# LEGOduino.net
KiCad netlist of a schematic drawn in EAGLE
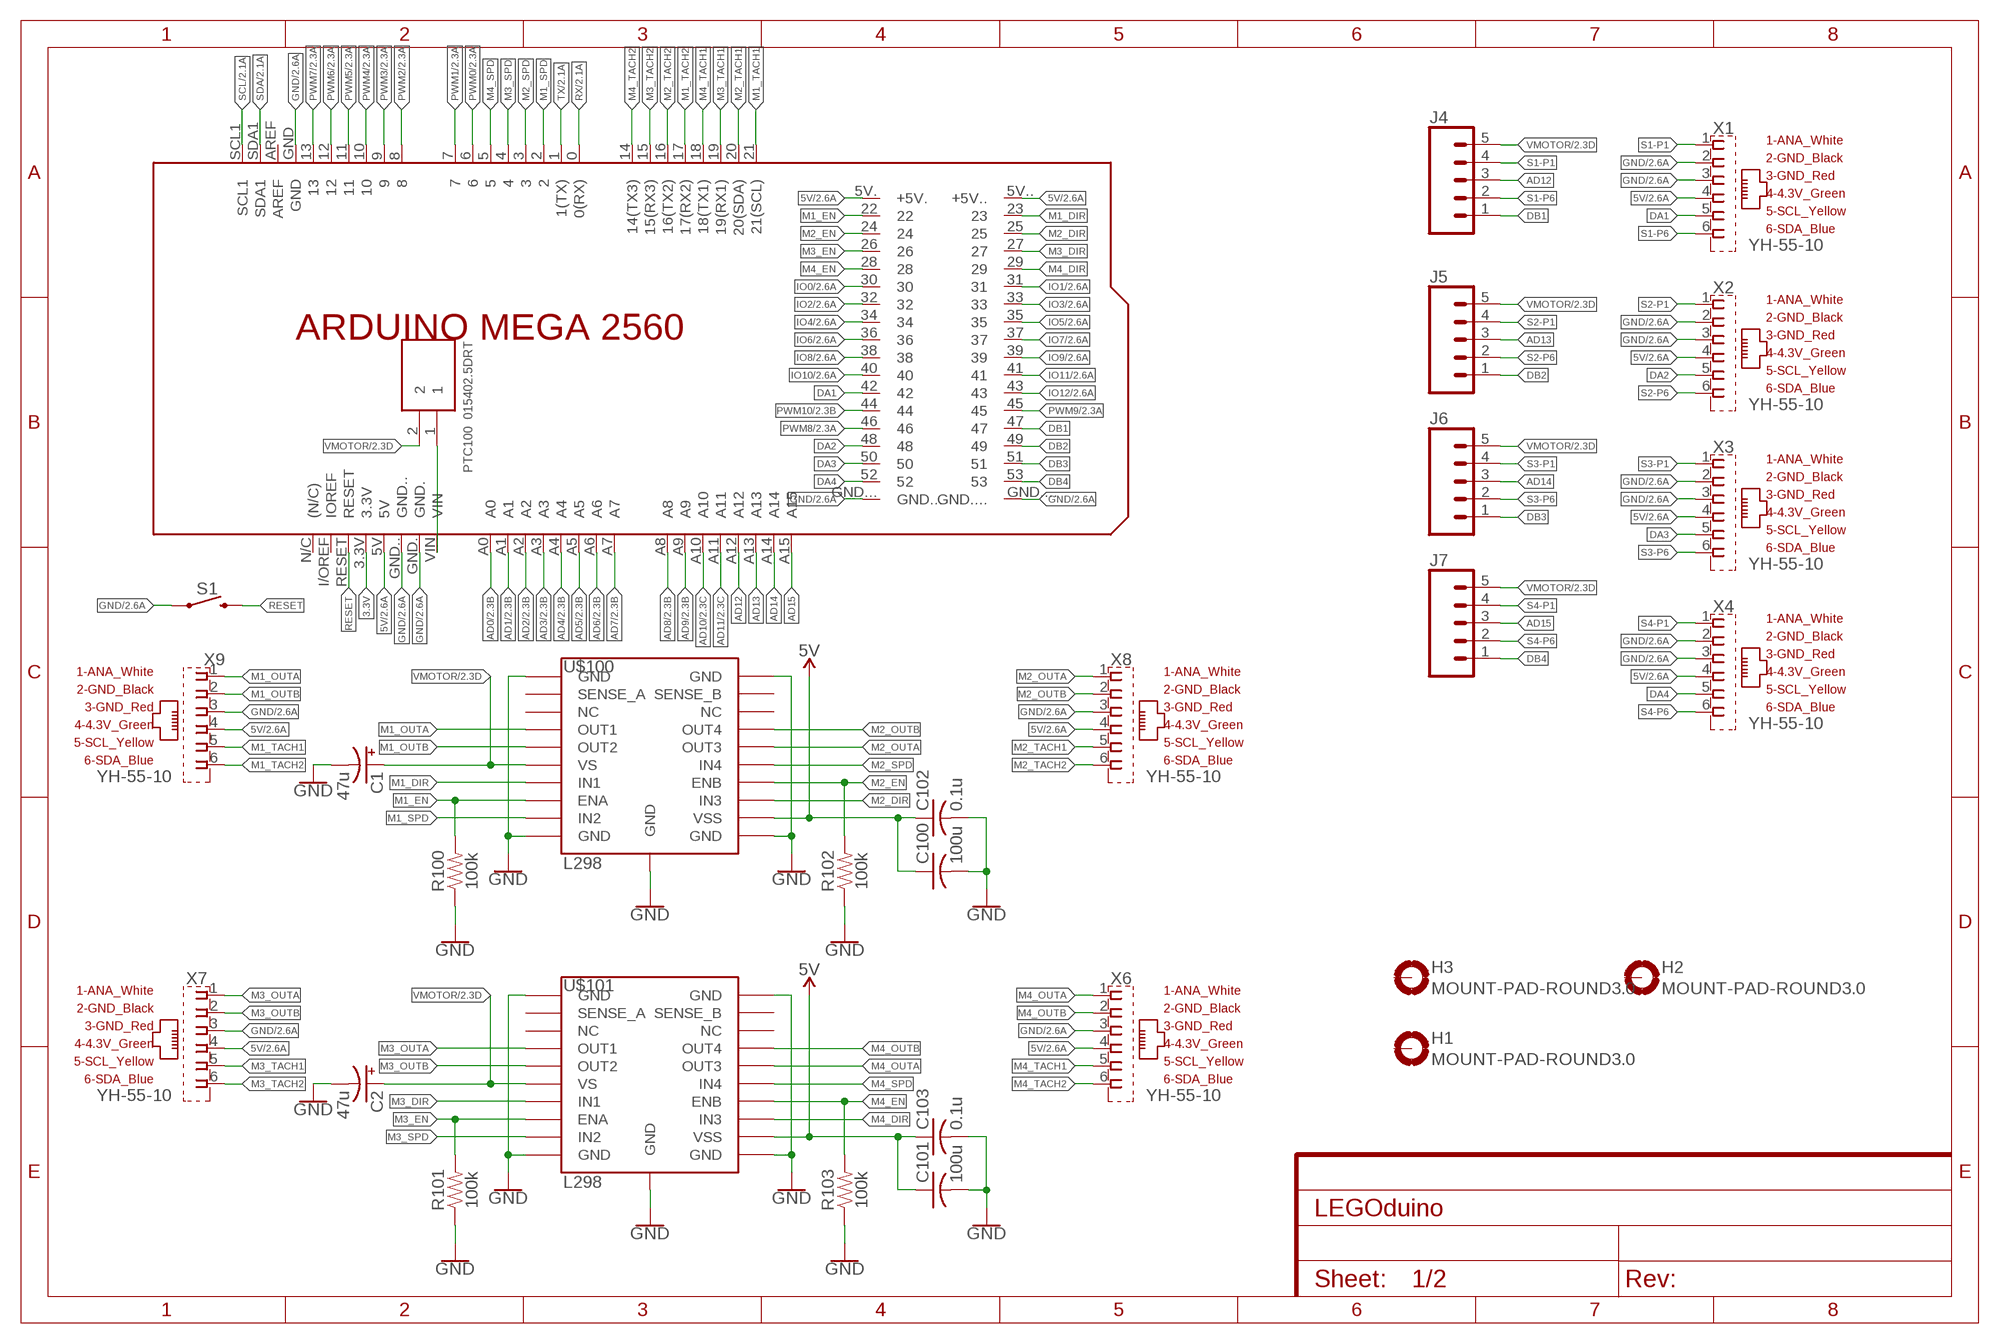
[diagram p0: schematic, sheet 1]
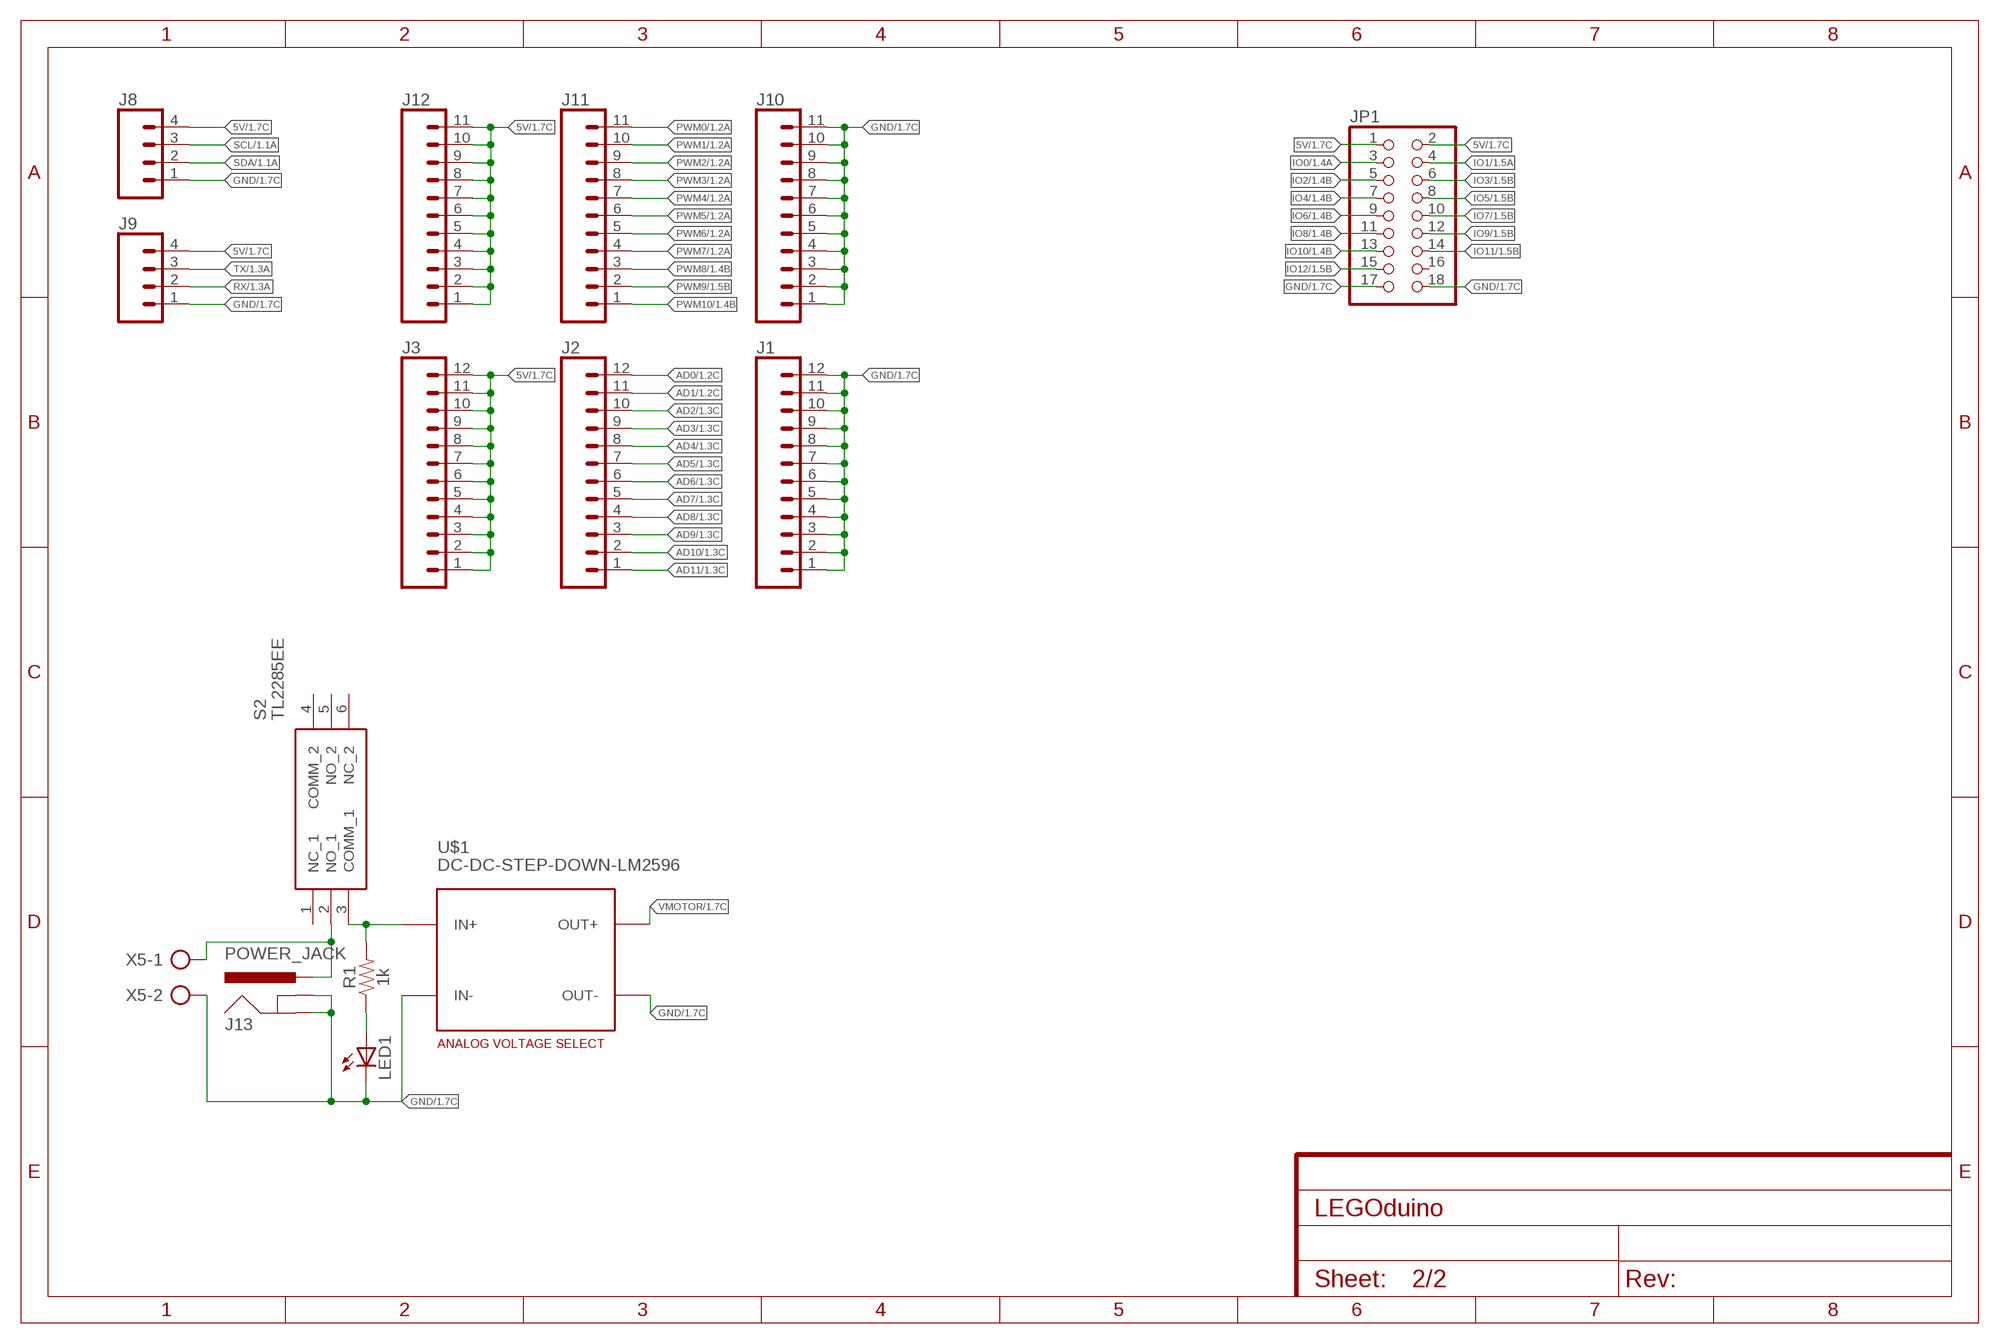
[diagram p1: schematic, sheet 2]

(export (version "E")
  (design (tool "Eeschema 10.0.6"))
  (components
    (comp (ref "J1")
      (value "CONN_12")
      (footprint "eagle-import:1X12")
      (libsource (lib "eagle-import") (part "CONN_12"))
    )
    (comp (ref "J2")
      (value "CONN_12")
      (footprint "eagle-import:1X12")
      (libsource (lib "eagle-import") (part "CONN_12"))
    )
    (comp (ref "J3")
      (value "CONN_12")
      (footprint "eagle-import:1X12")
      (libsource (lib "eagle-import") (part "CONN_12"))
    )
    (comp (ref "J8")
      (value "CONN_04")
      (footprint "eagle-import:1X04")
      (libsource (lib "eagle-import") (part "CONN_04"))
    )
    (comp (ref "J9")
      (value "CONN_04")
      (footprint "eagle-import:1X04")
      (libsource (lib "eagle-import") (part "CONN_04"))
    )
    (comp (ref "J10")
      (value "CONN_11")
      (footprint "eagle-import:1X11")
      (libsource (lib "eagle-import") (part "CONN_11"))
    )
    (comp (ref "J11")
      (value "CONN_11")
      (footprint "eagle-import:1X11")
      (libsource (lib "eagle-import") (part "CONN_11"))
    )
    (comp (ref "J12")
      (value "CONN_11")
      (footprint "eagle-import:1X11")
      (libsource (lib "eagle-import") (part "CONN_11"))
    )
    (comp (ref "J13")
      (value "POWER_JACK")
      (footprint "eagle-import:POWER_JACK_PTH")
      (libsource (lib "eagle-import") (part "POWER_JACK"))
    )
    (comp (ref "JP1")
      (value "PINHD-2X9")
      (footprint "eagle-import:2X09")
      (libsource (lib "eagle-import") (part "PINHD-2X9"))
    )
    (comp (ref "LED1")
      (value "LEDCHIP-LED0805")
      (footprint "eagle-import:CHIP-LED0805")
      (libsource (lib "eagle-import") (part "LEDCHIP-LED0805"))
    )
    (comp (ref "R1")
      (value "1k")
      (footprint "eagle-import:0805")
      (libsource (lib "eagle-import") (part "RESISTOR0805"))
    )
    (comp (ref "S2")
      (value "TL2285EE")
      (footprint "eagle-import:TL2285EE")
      (fields (field (name "MOUSER_PART_NUMBER") "612-TL2285EE"))
      (libsource (lib "eagle-import") (part "TL2285EE"))
    )
    (comp (ref "U$1")
      (value "DC-DC-STEP-DOWN-LM2596")
      (footprint "eagle-import:DC-DC-STEP-DOWN-LM2596")
      (libsource (lib "eagle-import") (part "DC-DC-STEP-DOWN-LM2596"))
    )
    (comp (ref "X5")
      (value "AK500/2-H")
      (footprint "eagle-import:AK500_2-H")
      (libsource (lib "eagle-import") (part "AK500/2-H"))
    )
    (comp (ref "C1")
      (value "47u")
      (footprint "eagle-import:CAPAE830X1050N")
      (libsource (lib "eagle-import") (part "C-POL-USECAP-8.5MM_"))
    )
    (comp (ref "C2")
      (value "47u")
      (footprint "eagle-import:CAPAE830X1050N")
      (libsource (lib "eagle-import") (part "C-POL-USECAP-8.5MM_"))
    )
    (comp (ref "C100")
      (value "100u")
      (footprint "eagle-import:C0805K")
      (libsource (lib "eagle-import") (part "C-USC0805K"))
    )
    (comp (ref "C101")
      (value "100u")
      (footprint "eagle-import:C0805K")
      (libsource (lib "eagle-import") (part "C-USC0805K"))
    )
    (comp (ref "C102")
      (value "0.1u")
      (footprint "eagle-import:C0805K")
      (libsource (lib "eagle-import") (part "C-USC0805K"))
    )
    (comp (ref "C103")
      (value "0.1u")
      (footprint "eagle-import:C0805K")
      (libsource (lib "eagle-import") (part "C-USC0805K"))
    )
    (comp (ref "H1")
      (value "MOUNT-PAD-ROUND3.0")
      (footprint "eagle-import:3,0-PAD")
      (libsource (lib "eagle-import") (part "MOUNT-PAD-ROUND3.0"))
    )
    (comp (ref "H2")
      (value "MOUNT-PAD-ROUND3.0")
      (footprint "eagle-import:3,0-PAD")
      (libsource (lib "eagle-import") (part "MOUNT-PAD-ROUND3.0"))
    )
    (comp (ref "H3")
      (value "MOUNT-PAD-ROUND3.0")
      (footprint "eagle-import:3,0-PAD")
      (libsource (lib "eagle-import") (part "MOUNT-PAD-ROUND3.0"))
    )
    (comp (ref "J4")
      (value "CONN_05")
      (footprint "eagle-import:1X05")
      (libsource (lib "eagle-import") (part "CONN_05"))
    )
    (comp (ref "J5")
      (value "CONN_05")
      (footprint "eagle-import:1X05")
      (libsource (lib "eagle-import") (part "CONN_05"))
    )
    (comp (ref "J6")
      (value "CONN_05")
      (footprint "eagle-import:1X05")
      (libsource (lib "eagle-import") (part "CONN_05"))
    )
    (comp (ref "J7")
      (value "CONN_05")
      (footprint "eagle-import:1X05")
      (libsource (lib "eagle-import") (part "CONN_05"))
    )
    (comp (ref "PCB100")
      (value "ARDUINO_MEGA2560")
      (footprint "eagle-import:ARDUINO_MEGA2560")
      (libsource (lib "eagle-import") (part "ARDUINO_MEGA2560"))
    )
    (comp (ref "PTC100")
      (value "015402.5DRT")
      (footprint "eagle-import:FUSM9750X381N")
      (fields
        (field (name "MOUSER_PART_NUMBER") "576-015402.5DRT")
        (field (name "RS_PART_NUMBER") "7382860P")
      )
      (libsource (lib "eagle-import") (part "015402.5DRT"))
    )
    (comp (ref "R100")
      (value "100k")
      (footprint "eagle-import:0805")
      (libsource (lib "eagle-import") (part "RESISTOR0805"))
    )
    (comp (ref "R101")
      (value "100k")
      (footprint "eagle-import:0805")
      (libsource (lib "eagle-import") (part "RESISTOR0805"))
    )
    (comp (ref "R102")
      (value "100k")
      (footprint "eagle-import:0805")
      (libsource (lib "eagle-import") (part "RESISTOR0805"))
    )
    (comp (ref "R103")
      (value "100k")
      (footprint "eagle-import:0805")
      (libsource (lib "eagle-import") (part "RESISTOR0805"))
    )
    (comp (ref "S1")
      (value "MOMENTARY-SWITCH-SPST-SMD-5.2MM")
      (footprint "eagle-import:TACTILE_SWITCH_SMD_5.2MM")
      (libsource (lib "eagle-import") (part "MOMENTARY-SWITCH-SPST-SMD-5.2MM"))
    )
    (comp (ref "U$100")
      (value "L298")
      (footprint "eagle-import:POWERSO20_L298_PAD")
      (libsource (lib "eagle-import") (part "L298_SMD_W_PAD"))
    )
    (comp (ref "U$101")
      (value "L298")
      (footprint "eagle-import:POWERSO20_L298_PAD")
      (libsource (lib "eagle-import") (part "L298_SMD_W_PAD"))
    )
    (comp (ref "X1")
      (value "YH-55-10")
      (footprint "eagle-import:YH-55-10")
      (libsource (lib "eagle-import") (part "YH-55-10"))
    )
    (comp (ref "X2")
      (value "YH-55-10")
      (footprint "eagle-import:YH-55-10")
      (libsource (lib "eagle-import") (part "YH-55-10"))
    )
    (comp (ref "X3")
      (value "YH-55-10")
      (footprint "eagle-import:YH-55-10")
      (libsource (lib "eagle-import") (part "YH-55-10"))
    )
    (comp (ref "X4")
      (value "YH-55-10")
      (footprint "eagle-import:YH-55-10")
      (libsource (lib "eagle-import") (part "YH-55-10"))
    )
    (comp (ref "X6")
      (value "YH-55-10")
      (footprint "eagle-import:YH-55-10")
      (libsource (lib "eagle-import") (part "YH-55-10"))
    )
    (comp (ref "X7")
      (value "YH-55-10")
      (footprint "eagle-import:YH-55-10")
      (libsource (lib "eagle-import") (part "YH-55-10"))
    )
    (comp (ref "X8")
      (value "YH-55-10")
      (footprint "eagle-import:YH-55-10")
      (libsource (lib "eagle-import") (part "YH-55-10"))
    )
    (comp (ref "X9")
      (value "YH-55-10")
      (footprint "eagle-import:YH-55-10")
      (libsource (lib "eagle-import") (part "YH-55-10"))
    )
  )
  (nets
    (net (code "1") (name "3.3V") (class "Default")
      (node (ref "PCB100") (pin "3.3V") (pinfunction "3.3V_3.3V") (pintype "bidirectional"))
    )
    (net (code "2") (name "5V") (class "Default")
      (node (ref "C100") (pin "1") (pinfunction "1_1") (pintype "passive"))
      (node (ref "C101") (pin "1") (pinfunction "1_1") (pintype "passive"))
      (node (ref "C102") (pin "1") (pinfunction "1_1") (pintype "passive"))
      (node (ref "C103") (pin "1") (pinfunction "1_1") (pintype "passive"))
      (node (ref "J12") (pin "1") (pinfunction "1_1") (pintype "passive"))
      (node (ref "J12") (pin "10") (pinfunction "10_10") (pintype "passive"))
      (node (ref "J12") (pin "11") (pinfunction "11_11") (pintype "passive"))
      (node (ref "J12") (pin "2") (pinfunction "2_2") (pintype "passive"))
      (node (ref "J12") (pin "3") (pinfunction "3_3") (pintype "passive"))
      (node (ref "J12") (pin "4") (pinfunction "4_4") (pintype "passive"))
      (node (ref "J12") (pin "5") (pinfunction "5_5") (pintype "passive"))
      (node (ref "J12") (pin "6") (pinfunction "6_6") (pintype "passive"))
      (node (ref "J12") (pin "7") (pinfunction "7_7") (pintype "passive"))
      (node (ref "J12") (pin "8") (pinfunction "8_8") (pintype "passive"))
      (node (ref "J12") (pin "9") (pinfunction "9_9") (pintype "passive"))
      (node (ref "J3") (pin "1") (pinfunction "1_1") (pintype "passive"))
      (node (ref "J3") (pin "10") (pinfunction "10_10") (pintype "passive"))
      (node (ref "J3") (pin "11") (pinfunction "11_11") (pintype "passive"))
      (node (ref "J3") (pin "12") (pinfunction "12_12") (pintype "passive"))
      (node (ref "J3") (pin "2") (pinfunction "2_2") (pintype "passive"))
      (node (ref "J3") (pin "3") (pinfunction "3_3") (pintype "passive"))
      (node (ref "J3") (pin "4") (pinfunction "4_4") (pintype "passive"))
      (node (ref "J3") (pin "5") (pinfunction "5_5") (pintype "passive"))
      (node (ref "J3") (pin "6") (pinfunction "6_6") (pintype "passive"))
      (node (ref "J3") (pin "7") (pinfunction "7_7") (pintype "passive"))
      (node (ref "J3") (pin "8") (pinfunction "8_8") (pintype "passive"))
      (node (ref "J3") (pin "9") (pinfunction "9_9") (pintype "passive"))
      (node (ref "J8") (pin "4") (pinfunction "4_4") (pintype "passive"))
      (node (ref "J9") (pin "4") (pinfunction "4_4") (pintype "passive"))
      (node (ref "JP1") (pin "1") (pinfunction "1_1") (pintype "passive"))
      (node (ref "JP1") (pin "2") (pinfunction "2_2") (pintype "passive"))
      (node (ref "PCB100") (pin "5V") (pinfunction "5V_5V") (pintype "bidirectional"))
      (node (ref "PCB100") (pin "5V.") (pinfunction "+5V._5V.") (pintype "bidirectional"))
      (node (ref "PCB100") (pin "5V..") (pinfunction "+5V.._5V..") (pintype "bidirectional"))
      (node (ref "U$100") (pin "12") (pinfunction "VSS_12") (pintype "bidirectional"))
      (node (ref "U$101") (pin "12") (pinfunction "VSS_12") (pintype "bidirectional"))
      (node (ref "X1") (pin "4") (pinfunction "4_4.3V_GREEN_4") (pintype "passive"))
      (node (ref "X2") (pin "4") (pinfunction "4_4.3V_GREEN_4") (pintype "passive"))
      (node (ref "X3") (pin "4") (pinfunction "4_4.3V_GREEN_4") (pintype "passive"))
      (node (ref "X4") (pin "4") (pinfunction "4_4.3V_GREEN_4") (pintype "passive"))
      (node (ref "X6") (pin "4") (pinfunction "4_4.3V_GREEN_4") (pintype "passive"))
      (node (ref "X7") (pin "4") (pinfunction "4_4.3V_GREEN_4") (pintype "passive"))
      (node (ref "X8") (pin "4") (pinfunction "4_4.3V_GREEN_4") (pintype "passive"))
      (node (ref "X9") (pin "4") (pinfunction "4_4.3V_GREEN_4") (pintype "passive"))
    )
    (net (code "3") (name "AD0") (class "Default")
      (node (ref "J2") (pin "12") (pinfunction "12_12") (pintype "passive"))
      (node (ref "PCB100") (pin "A0") (pinfunction "A0_A0") (pintype "bidirectional"))
    )
    (net (code "4") (name "AD1") (class "Default")
      (node (ref "J2") (pin "11") (pinfunction "11_11") (pintype "passive"))
      (node (ref "PCB100") (pin "A1") (pinfunction "A1_A1") (pintype "bidirectional"))
    )
    (net (code "5") (name "AD2") (class "Default")
      (node (ref "J2") (pin "10") (pinfunction "10_10") (pintype "passive"))
      (node (ref "PCB100") (pin "A2") (pinfunction "A2_A2") (pintype "bidirectional"))
    )
    (net (code "6") (name "AD3") (class "Default")
      (node (ref "J2") (pin "9") (pinfunction "9_9") (pintype "passive"))
      (node (ref "PCB100") (pin "A3") (pinfunction "A3_A3") (pintype "bidirectional"))
    )
    (net (code "7") (name "AD4") (class "Default")
      (node (ref "J2") (pin "8") (pinfunction "8_8") (pintype "passive"))
      (node (ref "PCB100") (pin "A4") (pinfunction "A4_A4") (pintype "bidirectional"))
    )
    (net (code "8") (name "AD5") (class "Default")
      (node (ref "J2") (pin "7") (pinfunction "7_7") (pintype "passive"))
      (node (ref "PCB100") (pin "A5") (pinfunction "A5_A5") (pintype "bidirectional"))
    )
    (net (code "9") (name "AD6") (class "Default")
      (node (ref "J2") (pin "6") (pinfunction "6_6") (pintype "passive"))
      (node (ref "PCB100") (pin "A6") (pinfunction "A6_A6") (pintype "bidirectional"))
    )
    (net (code "10") (name "AD7") (class "Default")
      (node (ref "J2") (pin "5") (pinfunction "5_5") (pintype "passive"))
      (node (ref "PCB100") (pin "A7") (pinfunction "A7_A7") (pintype "bidirectional"))
    )
    (net (code "11") (name "AD8") (class "Default")
      (node (ref "J2") (pin "4") (pinfunction "4_4") (pintype "passive"))
      (node (ref "PCB100") (pin "A8") (pinfunction "A8_A8") (pintype "bidirectional"))
    )
    (net (code "12") (name "AD9") (class "Default")
      (node (ref "J2") (pin "3") (pinfunction "3_3") (pintype "passive"))
      (node (ref "PCB100") (pin "A9") (pinfunction "A9_A9") (pintype "bidirectional"))
    )
    (net (code "13") (name "AD10") (class "Default")
      (node (ref "J2") (pin "2") (pinfunction "2_2") (pintype "passive"))
      (node (ref "PCB100") (pin "A10") (pinfunction "A10_A10") (pintype "bidirectional"))
    )
    (net (code "14") (name "AD11") (class "Default")
      (node (ref "J2") (pin "1") (pinfunction "1_1") (pintype "passive"))
      (node (ref "PCB100") (pin "A11") (pinfunction "A11_A11") (pintype "bidirectional"))
    )
    (net (code "15") (name "AD12") (class "Default")
      (node (ref "J4") (pin "3") (pinfunction "3_3") (pintype "passive"))
      (node (ref "PCB100") (pin "A12") (pinfunction "A12_A12") (pintype "bidirectional"))
    )
    (net (code "16") (name "AD13") (class "Default")
      (node (ref "J5") (pin "3") (pinfunction "3_3") (pintype "passive"))
      (node (ref "PCB100") (pin "A13") (pinfunction "A13_A13") (pintype "bidirectional"))
    )
    (net (code "17") (name "AD14") (class "Default")
      (node (ref "J6") (pin "3") (pinfunction "3_3") (pintype "passive"))
      (node (ref "PCB100") (pin "A14") (pinfunction "A14_A14") (pintype "bidirectional"))
    )
    (net (code "18") (name "AD15") (class "Default")
      (node (ref "J7") (pin "3") (pinfunction "3_3") (pintype "passive"))
      (node (ref "PCB100") (pin "A15") (pinfunction "A15_A15") (pintype "bidirectional"))
    )
    (net (code "19") (name "DA1") (class "Default")
      (node (ref "PCB100") (pin "42") (pinfunction "42_42") (pintype "bidirectional"))
      (node (ref "X1") (pin "5") (pinfunction "5_SCL_YELLOW_5") (pintype "passive"))
    )
    (net (code "20") (name "DA2") (class "Default")
      (node (ref "PCB100") (pin "48") (pinfunction "48_48") (pintype "bidirectional"))
      (node (ref "X2") (pin "5") (pinfunction "5_SCL_YELLOW_5") (pintype "passive"))
    )
    (net (code "21") (name "DA3") (class "Default")
      (node (ref "PCB100") (pin "50") (pinfunction "50_50") (pintype "bidirectional"))
      (node (ref "X3") (pin "5") (pinfunction "5_SCL_YELLOW_5") (pintype "passive"))
    )
    (net (code "22") (name "DA4") (class "Default")
      (node (ref "PCB100") (pin "52") (pinfunction "52_52") (pintype "bidirectional"))
      (node (ref "X4") (pin "5") (pinfunction "5_SCL_YELLOW_5") (pintype "passive"))
    )
    (net (code "23") (name "DB1") (class "Default")
      (node (ref "J4") (pin "1") (pinfunction "1_1") (pintype "passive"))
      (node (ref "PCB100") (pin "47") (pinfunction "47_47") (pintype "bidirectional"))
    )
    (net (code "24") (name "DB2") (class "Default")
      (node (ref "J5") (pin "1") (pinfunction "1_1") (pintype "passive"))
      (node (ref "PCB100") (pin "49") (pinfunction "49_49") (pintype "bidirectional"))
    )
    (net (code "25") (name "DB3") (class "Default")
      (node (ref "J6") (pin "1") (pinfunction "1_1") (pintype "passive"))
      (node (ref "PCB100") (pin "51") (pinfunction "51_51") (pintype "bidirectional"))
    )
    (net (code "26") (name "DB4") (class "Default")
      (node (ref "J7") (pin "1") (pinfunction "1_1") (pintype "passive"))
      (node (ref "PCB100") (pin "53") (pinfunction "53_53") (pintype "bidirectional"))
    )
    (net (code "27") (name "GND") (class "Default")
      (node (ref "C1") (pin "2") (pinfunction "-_2") (pintype "passive"))
      (node (ref "C100") (pin "2") (pinfunction "2_2") (pintype "passive"))
      (node (ref "C101") (pin "2") (pinfunction "2_2") (pintype "passive"))
      (node (ref "C102") (pin "2") (pinfunction "2_2") (pintype "passive"))
      (node (ref "C103") (pin "2") (pinfunction "2_2") (pintype "passive"))
      (node (ref "C2") (pin "2") (pinfunction "-_2") (pintype "passive"))
      (node (ref "J1") (pin "1") (pinfunction "1_1") (pintype "passive"))
      (node (ref "J1") (pin "10") (pinfunction "10_10") (pintype "passive"))
      (node (ref "J1") (pin "11") (pinfunction "11_11") (pintype "passive"))
      (node (ref "J1") (pin "12") (pinfunction "12_12") (pintype "passive"))
      (node (ref "J1") (pin "2") (pinfunction "2_2") (pintype "passive"))
      (node (ref "J1") (pin "3") (pinfunction "3_3") (pintype "passive"))
      (node (ref "J1") (pin "4") (pinfunction "4_4") (pintype "passive"))
      (node (ref "J1") (pin "5") (pinfunction "5_5") (pintype "passive"))
      (node (ref "J1") (pin "6") (pinfunction "6_6") (pintype "passive"))
      (node (ref "J1") (pin "7") (pinfunction "7_7") (pintype "passive"))
      (node (ref "J1") (pin "8") (pinfunction "8_8") (pintype "passive"))
      (node (ref "J1") (pin "9") (pinfunction "9_9") (pintype "passive"))
      (node (ref "J10") (pin "1") (pinfunction "1_1") (pintype "passive"))
      (node (ref "J10") (pin "10") (pinfunction "10_10") (pintype "passive"))
      (node (ref "J10") (pin "11") (pinfunction "11_11") (pintype "passive"))
      (node (ref "J10") (pin "2") (pinfunction "2_2") (pintype "passive"))
      (node (ref "J10") (pin "3") (pinfunction "3_3") (pintype "passive"))
      (node (ref "J10") (pin "4") (pinfunction "4_4") (pintype "passive"))
      (node (ref "J10") (pin "5") (pinfunction "5_5") (pintype "passive"))
      (node (ref "J10") (pin "6") (pinfunction "6_6") (pintype "passive"))
      (node (ref "J10") (pin "7") (pinfunction "7_7") (pintype "passive"))
      (node (ref "J10") (pin "8") (pinfunction "8_8") (pintype "passive"))
      (node (ref "J10") (pin "9") (pinfunction "9_9") (pintype "passive"))
      (node (ref "J13") (pin "GND") (pinfunction "GND_GND") (pintype "bidirectional"))
      (node (ref "J13") (pin "GNDBREAK") (pinfunction "GNDBREAK_GNDBREAK") (pintype "bidirectional"))
      (node (ref "J8") (pin "1") (pinfunction "1_1") (pintype "passive"))
      (node (ref "J9") (pin "1") (pinfunction "1_1") (pintype "passive"))
      (node (ref "JP1") (pin "17") (pinfunction "17_17") (pintype "passive"))
      (node (ref "JP1") (pin "18") (pinfunction "18_18") (pintype "passive"))
      (node (ref "LED1") (pin "C") (pinfunction "C_C") (pintype "passive"))
      (node (ref "PCB100") (pin "GND") (pinfunction "GND_GND") (pintype "bidirectional"))
      (node (ref "PCB100") (pin "GND.") (pinfunction "GND._GND.") (pintype "bidirectional"))
      (node (ref "PCB100") (pin "GND..") (pinfunction "GND.._GND..") (pintype "bidirectional"))
      (node (ref "PCB100") (pin "GND...") (pinfunction "GND..._GND...") (pintype "bidirectional"))
      (node (ref "PCB100") (pin "GND....") (pinfunction "GND...._GND....") (pintype "bidirectional"))
      (node (ref "R100") (pin "1") (pinfunction "1_1") (pintype "passive"))
      (node (ref "R101") (pin "1") (pinfunction "1_1") (pintype "passive"))
      (node (ref "R102") (pin "1") (pinfunction "1_1") (pintype "passive"))
      (node (ref "R103") (pin "1") (pinfunction "1_1") (pintype "passive"))
      (node (ref "S1") (pin "1") (pinfunction "1_1") (pintype "passive"))
      (node (ref "U$1") (pin "IN-") (pinfunction "IN-_IN-") (pintype "bidirectional"))
      (node (ref "U$1") (pin "OUT-") (pinfunction "OUT-_OUT-") (pintype "bidirectional"))
      (node (ref "U$100") (pin "1") (pinfunction "GND_1") (pintype "bidirectional"))
      (node (ref "U$100") (pin "10") (pinfunction "GND_10") (pintype "bidirectional"))
      (node (ref "U$100") (pin "11") (pinfunction "GND_11") (pintype "bidirectional"))
      (node (ref "U$100") (pin "20") (pinfunction "GND_20") (pintype "bidirectional"))
      (node (ref "U$100") (pin "PAD") (pinfunction "GND_PAD") (pintype "bidirectional"))
      (node (ref "U$101") (pin "1") (pinfunction "GND_1") (pintype "bidirectional"))
      (node (ref "U$101") (pin "10") (pinfunction "GND_10") (pintype "bidirectional"))
      (node (ref "U$101") (pin "11") (pinfunction "GND_11") (pintype "bidirectional"))
      (node (ref "U$101") (pin "20") (pinfunction "GND_20") (pintype "bidirectional"))
      (node (ref "U$101") (pin "PAD") (pinfunction "GND_PAD") (pintype "bidirectional"))
      (node (ref "X1") (pin "2") (pinfunction "2_GND_BLACK_2") (pintype "passive"))
      (node (ref "X1") (pin "3") (pinfunction "3_GND_RED_3") (pintype "passive"))
      (node (ref "X2") (pin "2") (pinfunction "2_GND_BLACK_2") (pintype "passive"))
      (node (ref "X2") (pin "3") (pinfunction "3_GND_RED_3") (pintype "passive"))
      (node (ref "X3") (pin "2") (pinfunction "2_GND_BLACK_2") (pintype "passive"))
      (node (ref "X3") (pin "3") (pinfunction "3_GND_RED_3") (pintype "passive"))
      (node (ref "X4") (pin "2") (pinfunction "2_GND_BLACK_2") (pintype "passive"))
      (node (ref "X4") (pin "3") (pinfunction "3_GND_RED_3") (pintype "passive"))
      (node (ref "X5") (pin "2") (pinfunction "KL_2") (pintype "passive"))
      (node (ref "X6") (pin "3") (pinfunction "3_GND_RED_3") (pintype "passive"))
      (node (ref "X7") (pin "3") (pinfunction "3_GND_RED_3") (pintype "passive"))
      (node (ref "X8") (pin "3") (pinfunction "3_GND_RED_3") (pintype "passive"))
      (node (ref "X9") (pin "3") (pinfunction "3_GND_RED_3") (pintype "passive"))
    )
    (net (code "28") (name "IO0") (class "Default")
      (node (ref "JP1") (pin "3") (pinfunction "3_3") (pintype "passive"))
      (node (ref "PCB100") (pin "30") (pinfunction "30_30") (pintype "bidirectional"))
    )
    (net (code "29") (name "IO1") (class "Default")
      (node (ref "JP1") (pin "4") (pinfunction "4_4") (pintype "passive"))
      (node (ref "PCB100") (pin "31") (pinfunction "31_31") (pintype "bidirectional"))
    )
    (net (code "30") (name "IO2") (class "Default")
      (node (ref "JP1") (pin "5") (pinfunction "5_5") (pintype "passive"))
      (node (ref "PCB100") (pin "32") (pinfunction "32_32") (pintype "bidirectional"))
    )
    (net (code "31") (name "IO3") (class "Default")
      (node (ref "JP1") (pin "6") (pinfunction "6_6") (pintype "passive"))
      (node (ref "PCB100") (pin "33") (pinfunction "33_33") (pintype "bidirectional"))
    )
    (net (code "32") (name "IO4") (class "Default")
      (node (ref "JP1") (pin "7") (pinfunction "7_7") (pintype "passive"))
      (node (ref "PCB100") (pin "34") (pinfunction "34_34") (pintype "bidirectional"))
    )
    (net (code "33") (name "IO5") (class "Default")
      (node (ref "JP1") (pin "8") (pinfunction "8_8") (pintype "passive"))
      (node (ref "PCB100") (pin "35") (pinfunction "35_35") (pintype "bidirectional"))
    )
    (net (code "34") (name "IO6") (class "Default")
      (node (ref "JP1") (pin "9") (pinfunction "9_9") (pintype "passive"))
      (node (ref "PCB100") (pin "36") (pinfunction "36_36") (pintype "bidirectional"))
    )
    (net (code "35") (name "IO7") (class "Default")
      (node (ref "JP1") (pin "10") (pinfunction "10_10") (pintype "passive"))
      (node (ref "PCB100") (pin "37") (pinfunction "37_37") (pintype "bidirectional"))
    )
    (net (code "36") (name "IO8") (class "Default")
      (node (ref "JP1") (pin "11") (pinfunction "11_11") (pintype "passive"))
      (node (ref "PCB100") (pin "38") (pinfunction "38_38") (pintype "bidirectional"))
    )
    (net (code "37") (name "IO9") (class "Default")
      (node (ref "JP1") (pin "12") (pinfunction "12_12") (pintype "passive"))
      (node (ref "PCB100") (pin "39") (pinfunction "39_39") (pintype "bidirectional"))
    )
    (net (code "38") (name "IO10") (class "Default")
      (node (ref "JP1") (pin "13") (pinfunction "13_13") (pintype "passive"))
      (node (ref "PCB100") (pin "40") (pinfunction "40_40") (pintype "bidirectional"))
    )
    (net (code "39") (name "IO11") (class "Default")
      (node (ref "JP1") (pin "14") (pinfunction "14_14") (pintype "passive"))
      (node (ref "PCB100") (pin "41") (pinfunction "41_41") (pintype "bidirectional"))
    )
    (net (code "40") (name "IO12") (class "Default")
      (node (ref "JP1") (pin "15") (pinfunction "15_15") (pintype "passive"))
      (node (ref "PCB100") (pin "43") (pinfunction "43_43") (pintype "bidirectional"))
    )
    (net (code "41") (name "M1_DIR") (class "Default")
      (node (ref "PCB100") (pin "23") (pinfunction "23_23") (pintype "bidirectional"))
      (node (ref "U$100") (pin "7") (pinfunction "IN1_7") (pintype "bidirectional"))
    )
    (net (code "42") (name "M1_EN") (class "Default")
      (node (ref "PCB100") (pin "22") (pinfunction "22_22") (pintype "bidirectional"))
      (node (ref "R100") (pin "2") (pinfunction "2_2") (pintype "passive"))
      (node (ref "U$100") (pin "8") (pinfunction "ENA_8") (pintype "bidirectional"))
    )
    (net (code "43") (name "M1_OUTA") (class "Default")
      (node (ref "U$100") (pin "4") (pinfunction "OUT1_4") (pintype "bidirectional"))
      (node (ref "X9") (pin "1") (pinfunction "1_ANA_WHITE_1") (pintype "passive"))
    )
    (net (code "44") (name "M1_OUTB") (class "Default")
      (node (ref "U$100") (pin "5") (pinfunction "OUT2_5") (pintype "bidirectional"))
      (node (ref "X9") (pin "2") (pinfunction "2_GND_BLACK_2") (pintype "passive"))
    )
    (net (code "45") (name "M1_SPD") (class "Default")
      (node (ref "PCB100") (pin "2") (pinfunction "2_2") (pintype "bidirectional"))
      (node (ref "U$100") (pin "9") (pinfunction "IN2_9") (pintype "bidirectional"))
    )
    (net (code "46") (name "M1_TACH1") (class "Default")
      (node (ref "PCB100") (pin "21") (pinfunction "21(SCL)_21") (pintype "bidirectional"))
      (node (ref "X9") (pin "5") (pinfunction "5_SCL_YELLOW_5") (pintype "passive"))
    )
    (net (code "47") (name "M1_TACH2") (class "Default")
      (node (ref "PCB100") (pin "17") (pinfunction "17(RX2)_17") (pintype "bidirectional"))
      (node (ref "X9") (pin "6") (pinfunction "6_SDA_BLUE_6") (pintype "passive"))
    )
    (net (code "48") (name "M2_DIR") (class "Default")
      (node (ref "PCB100") (pin "25") (pinfunction "25_25") (pintype "bidirectional"))
      (node (ref "U$100") (pin "13") (pinfunction "IN3_13") (pintype "bidirectional"))
    )
    (net (code "49") (name "M2_EN") (class "Default")
      (node (ref "PCB100") (pin "24") (pinfunction "24_24") (pintype "bidirectional"))
      (node (ref "R102") (pin "2") (pinfunction "2_2") (pintype "passive"))
      (node (ref "U$100") (pin "14") (pinfunction "ENB_14") (pintype "bidirectional"))
    )
    (net (code "50") (name "M2_OUTA") (class "Default")
      (node (ref "U$100") (pin "16") (pinfunction "OUT3_16") (pintype "bidirectional"))
      (node (ref "X8") (pin "1") (pinfunction "1_ANA_WHITE_1") (pintype "passive"))
    )
    (net (code "51") (name "M2_OUTB") (class "Default")
      (node (ref "U$100") (pin "17") (pinfunction "OUT4_17") (pintype "bidirectional"))
      (node (ref "X8") (pin "2") (pinfunction "2_GND_BLACK_2") (pintype "passive"))
    )
    (net (code "52") (name "M2_SPD") (class "Default")
      (node (ref "PCB100") (pin "3") (pinfunction "3_3") (pintype "bidirectional"))
      (node (ref "U$100") (pin "15") (pinfunction "IN4_15") (pintype "bidirectional"))
    )
    (net (code "53") (name "M2_TACH1") (class "Default")
      (node (ref "PCB100") (pin "20") (pinfunction "20(SDA)_20") (pintype "bidirectional"))
      (node (ref "X8") (pin "5") (pinfunction "5_SCL_YELLOW_5") (pintype "passive"))
    )
    (net (code "54") (name "M2_TACH2") (class "Default")
      (node (ref "PCB100") (pin "16") (pinfunction "16(TX2)_16") (pintype "bidirectional"))
      (node (ref "X8") (pin "6") (pinfunction "6_SDA_BLUE_6") (pintype "passive"))
    )
    (net (code "55") (name "M3_DIR") (class "Default")
      (node (ref "PCB100") (pin "27") (pinfunction "27_27") (pintype "bidirectional"))
      (node (ref "U$101") (pin "7") (pinfunction "IN1_7") (pintype "bidirectional"))
    )
    (net (code "56") (name "M3_EN") (class "Default")
      (node (ref "PCB100") (pin "26") (pinfunction "26_26") (pintype "bidirectional"))
      (node (ref "R101") (pin "2") (pinfunction "2_2") (pintype "passive"))
      (node (ref "U$101") (pin "8") (pinfunction "ENA_8") (pintype "bidirectional"))
    )
    (net (code "57") (name "M3_OUTA") (class "Default")
      (node (ref "U$101") (pin "4") (pinfunction "OUT1_4") (pintype "bidirectional"))
      (node (ref "X7") (pin "1") (pinfunction "1_ANA_WHITE_1") (pintype "passive"))
    )
    (net (code "58") (name "M3_OUTB") (class "Default")
      (node (ref "U$101") (pin "5") (pinfunction "OUT2_5") (pintype "bidirectional"))
      (node (ref "X7") (pin "2") (pinfunction "2_GND_BLACK_2") (pintype "passive"))
    )
    (net (code "59") (name "M3_SPD") (class "Default")
      (node (ref "PCB100") (pin "4") (pinfunction "4_4") (pintype "bidirectional"))
      (node (ref "U$101") (pin "9") (pinfunction "IN2_9") (pintype "bidirectional"))
    )
    (net (code "60") (name "M3_TACH1") (class "Default")
      (node (ref "PCB100") (pin "19") (pinfunction "19(RX1)_19") (pintype "bidirectional"))
      (node (ref "X7") (pin "5") (pinfunction "5_SCL_YELLOW_5") (pintype "passive"))
    )
    (net (code "61") (name "M3_TACH2") (class "Default")
      (node (ref "PCB100") (pin "15") (pinfunction "15(RX3)_15") (pintype "bidirectional"))
      (node (ref "X7") (pin "6") (pinfunction "6_SDA_BLUE_6") (pintype "passive"))
    )
    (net (code "62") (name "M4_DIR") (class "Default")
      (node (ref "PCB100") (pin "29") (pinfunction "29_29") (pintype "bidirectional"))
      (node (ref "U$101") (pin "13") (pinfunction "IN3_13") (pintype "bidirectional"))
    )
    (net (code "63") (name "M4_EN") (class "Default")
      (node (ref "PCB100") (pin "28") (pinfunction "28_28") (pintype "bidirectional"))
      (node (ref "R103") (pin "2") (pinfunction "2_2") (pintype "passive"))
      (node (ref "U$101") (pin "14") (pinfunction "ENB_14") (pintype "bidirectional"))
    )
    (net (code "64") (name "M4_OUTA") (class "Default")
      (node (ref "U$101") (pin "16") (pinfunction "OUT3_16") (pintype "bidirectional"))
      (node (ref "X6") (pin "1") (pinfunction "1_ANA_WHITE_1") (pintype "passive"))
    )
    (net (code "65") (name "M4_OUTB") (class "Default")
      (node (ref "U$101") (pin "17") (pinfunction "OUT4_17") (pintype "bidirectional"))
      (node (ref "X6") (pin "2") (pinfunction "2_GND_BLACK_2") (pintype "passive"))
    )
    (net (code "66") (name "M4_SPD") (class "Default")
      (node (ref "PCB100") (pin "5") (pinfunction "5_5") (pintype "bidirectional"))
      (node (ref "U$101") (pin "15") (pinfunction "IN4_15") (pintype "bidirectional"))
    )
    (net (code "67") (name "M4_TACH1") (class "Default")
      (node (ref "PCB100") (pin "18") (pinfunction "18(TX1)_18") (pintype "bidirectional"))
      (node (ref "X6") (pin "5") (pinfunction "5_SCL_YELLOW_5") (pintype "passive"))
    )
    (net (code "68") (name "M4_TACH2") (class "Default")
      (node (ref "PCB100") (pin "14") (pinfunction "14(TX3)_14") (pintype "bidirectional"))
      (node (ref "X6") (pin "6") (pinfunction "6_SDA_BLUE_6") (pintype "passive"))
    )
    (net (code "69") (name "Net-(LED1-PadA)") (class "Default")
      (node (ref "LED1") (pin "A") (pinfunction "A_A") (pintype "passive"))
      (node (ref "R1") (pin "1") (pinfunction "1_1") (pintype "passive"))
    )
    (net (code "70") (name "Net-(PCB100-PadVIN)") (class "Default")
      (node (ref "PCB100") (pin "VIN") (pinfunction "VIN_VIN") (pintype "bidirectional"))
      (node (ref "PTC100") (pin "1") (pinfunction "1_1") (pintype "bidirectional"))
    )
    (net (code "71") (name "Net-(S2-COMM_1)") (class "Default")
      (node (ref "R1") (pin "2") (pinfunction "2_2") (pintype "passive"))
      (node (ref "S2") (pin "3") (pinfunction "COMM_1_3") (pintype "bidirectional"))
      (node (ref "U$1") (pin "IN+") (pinfunction "IN+_IN+") (pintype "bidirectional"))
    )
    (net (code "72") (name "Net-(S2-NO_1)") (class "Default")
      (node (ref "J13") (pin "PWR") (pinfunction "PWR_PWR") (pintype "bidirectional"))
      (node (ref "S2") (pin "2") (pinfunction "NO_1_2") (pintype "bidirectional"))
      (node (ref "X5") (pin "1") (pinfunction "KL_1") (pintype "passive"))
    )
    (net (code "73") (name "PWM0") (class "Default")
      (node (ref "J11") (pin "11") (pinfunction "11_11") (pintype "passive"))
      (node (ref "PCB100") (pin "6") (pinfunction "6_6") (pintype "bidirectional"))
    )
    (net (code "74") (name "PWM1") (class "Default")
      (node (ref "J11") (pin "10") (pinfunction "10_10") (pintype "passive"))
      (node (ref "PCB100") (pin "7") (pinfunction "7_7") (pintype "bidirectional"))
    )
    (net (code "75") (name "PWM2") (class "Default")
      (node (ref "J11") (pin "9") (pinfunction "9_9") (pintype "passive"))
      (node (ref "PCB100") (pin "8") (pinfunction "8_8") (pintype "bidirectional"))
    )
    (net (code "76") (name "PWM3") (class "Default")
      (node (ref "J11") (pin "8") (pinfunction "8_8") (pintype "passive"))
      (node (ref "PCB100") (pin "9") (pinfunction "9_9") (pintype "bidirectional"))
    )
    (net (code "77") (name "PWM4") (class "Default")
      (node (ref "J11") (pin "7") (pinfunction "7_7") (pintype "passive"))
      (node (ref "PCB100") (pin "10") (pinfunction "10_10") (pintype "bidirectional"))
    )
    (net (code "78") (name "PWM5") (class "Default")
      (node (ref "J11") (pin "6") (pinfunction "6_6") (pintype "passive"))
      (node (ref "PCB100") (pin "11") (pinfunction "11_11") (pintype "bidirectional"))
    )
    (net (code "79") (name "PWM6") (class "Default")
      (node (ref "J11") (pin "5") (pinfunction "5_5") (pintype "passive"))
      (node (ref "PCB100") (pin "12") (pinfunction "12_12") (pintype "bidirectional"))
    )
    (net (code "80") (name "PWM7") (class "Default")
      (node (ref "J11") (pin "4") (pinfunction "4_4") (pintype "passive"))
      (node (ref "PCB100") (pin "13") (pinfunction "13_13") (pintype "bidirectional"))
    )
    (net (code "81") (name "PWM8") (class "Default")
      (node (ref "J11") (pin "3") (pinfunction "3_3") (pintype "passive"))
      (node (ref "PCB100") (pin "46") (pinfunction "46_46") (pintype "bidirectional"))
    )
    (net (code "82") (name "PWM9") (class "Default")
      (node (ref "J11") (pin "2") (pinfunction "2_2") (pintype "passive"))
      (node (ref "PCB100") (pin "45") (pinfunction "45_45") (pintype "bidirectional"))
    )
    (net (code "83") (name "PWM10") (class "Default")
      (node (ref "J11") (pin "1") (pinfunction "1_1") (pintype "passive"))
      (node (ref "PCB100") (pin "44") (pinfunction "44_44") (pintype "bidirectional"))
    )
    (net (code "84") (name "RESET") (class "Default")
      (node (ref "PCB100") (pin "RESET") (pinfunction "RESET_RESET") (pintype "bidirectional"))
      (node (ref "S1") (pin "3") (pinfunction "2_3") (pintype "passive"))
    )
    (net (code "85") (name "RX") (class "Default")
      (node (ref "J9") (pin "2") (pinfunction "2_2") (pintype "passive"))
      (node (ref "PCB100") (pin "0") (pinfunction "0(RX)_0") (pintype "bidirectional"))
    )
    (net (code "86") (name "S1-P1") (class "Default")
      (node (ref "J4") (pin "4") (pinfunction "4_4") (pintype "passive"))
      (node (ref "X1") (pin "1") (pinfunction "1_ANA_WHITE_1") (pintype "passive"))
    )
    (net (code "87") (name "S1-P6") (class "Default")
      (node (ref "J4") (pin "2") (pinfunction "2_2") (pintype "passive"))
      (node (ref "X1") (pin "6") (pinfunction "6_SDA_BLUE_6") (pintype "passive"))
    )
    (net (code "88") (name "S2-P1") (class "Default")
      (node (ref "J5") (pin "4") (pinfunction "4_4") (pintype "passive"))
      (node (ref "X2") (pin "1") (pinfunction "1_ANA_WHITE_1") (pintype "passive"))
    )
    (net (code "89") (name "S2-P6") (class "Default")
      (node (ref "J5") (pin "2") (pinfunction "2_2") (pintype "passive"))
      (node (ref "X2") (pin "6") (pinfunction "6_SDA_BLUE_6") (pintype "passive"))
    )
    (net (code "90") (name "S3-P1") (class "Default")
      (node (ref "J6") (pin "4") (pinfunction "4_4") (pintype "passive"))
      (node (ref "X3") (pin "1") (pinfunction "1_ANA_WHITE_1") (pintype "passive"))
    )
    (net (code "91") (name "S3-P6") (class "Default")
      (node (ref "J6") (pin "2") (pinfunction "2_2") (pintype "passive"))
      (node (ref "X3") (pin "6") (pinfunction "6_SDA_BLUE_6") (pintype "passive"))
    )
    (net (code "92") (name "S4-P1") (class "Default")
      (node (ref "J7") (pin "4") (pinfunction "4_4") (pintype "passive"))
      (node (ref "X4") (pin "1") (pinfunction "1_ANA_WHITE_1") (pintype "passive"))
    )
    (net (code "93") (name "S4-P6") (class "Default")
      (node (ref "J7") (pin "2") (pinfunction "2_2") (pintype "passive"))
      (node (ref "X4") (pin "6") (pinfunction "6_SDA_BLUE_6") (pintype "passive"))
    )
    (net (code "94") (name "SCL") (class "Default")
      (node (ref "J8") (pin "3") (pinfunction "3_3") (pintype "passive"))
      (node (ref "PCB100") (pin "SCL1") (pinfunction "SCL1_SCL1") (pintype "bidirectional"))
    )
    (net (code "95") (name "SDA") (class "Default")
      (node (ref "J8") (pin "2") (pinfunction "2_2") (pintype "passive"))
      (node (ref "PCB100") (pin "SDA1") (pinfunction "SDA1_SDA1") (pintype "bidirectional"))
    )
    (net (code "96") (name "TX") (class "Default")
      (node (ref "J9") (pin "3") (pinfunction "3_3") (pintype "passive"))
      (node (ref "PCB100") (pin "1") (pinfunction "1(TX)_1") (pintype "bidirectional"))
    )
    (net (code "97") (name "VMOTOR") (class "Default")
      (node (ref "C1") (pin "1") (pinfunction "+_1") (pintype "passive"))
      (node (ref "C2") (pin "1") (pinfunction "+_1") (pintype "passive"))
      (node (ref "J4") (pin "5") (pinfunction "5_5") (pintype "passive"))
      (node (ref "J5") (pin "5") (pinfunction "5_5") (pintype "passive"))
      (node (ref "J6") (pin "5") (pinfunction "5_5") (pintype "passive"))
      (node (ref "J7") (pin "5") (pinfunction "5_5") (pintype "passive"))
      (node (ref "PTC100") (pin "2") (pinfunction "2_2") (pintype "bidirectional"))
      (node (ref "U$1") (pin "OUT+") (pinfunction "OUT+_OUT+") (pintype "bidirectional"))
      (node (ref "U$100") (pin "6") (pinfunction "VS_6") (pintype "bidirectional"))
      (node (ref "U$101") (pin "6") (pinfunction "VS_6") (pintype "bidirectional"))
    )
    (net (code "98") (name "unconnected-(H1-MOUNT-PadB3,0)") (class "Default")
      (node (ref "H1") (pin "B3,0") (pinfunction "MOUNT_B3,0") (pintype "passive"))
    )
    (net (code "99") (name "unconnected-(H2-MOUNT-PadB3,0)") (class "Default")
      (node (ref "H2") (pin "B3,0") (pinfunction "MOUNT_B3,0") (pintype "passive"))
    )
    (net (code "100") (name "unconnected-(H3-MOUNT-PadB3,0)") (class "Default")
      (node (ref "H3") (pin "B3,0") (pinfunction "MOUNT_B3,0") (pintype "passive"))
    )
    (net (code "101") (name "unconnected-(JP1-Pad16)") (class "Default")
      (node (ref "JP1") (pin "16") (pinfunction "16_16") (pintype "passive"))
    )
    (net (code "102") (name "unconnected-(PCB100-(N{slash}C)-PadN{slash}C)") (class "Default")
      (node (ref "PCB100") (pin "N/C") (pinfunction "(N/C)_N/C") (pintype "bidirectional"))
    )
    (net (code "103") (name "unconnected-(PCB100-IOREF-PadI{slash}OREF)") (class "Default")
      (node (ref "PCB100") (pin "I/OREF") (pinfunction "IOREF_I/OREF") (pintype "bidirectional"))
    )
    (net (code "104") (name "unconnected-(PCB100-PadAREF)") (class "Default")
      (node (ref "PCB100") (pin "AREF") (pinfunction "AREF_AREF") (pintype "bidirectional"))
    )
    (net (code "105") (name "unconnected-(S2-COMM_2-Pad4)") (class "Default")
      (node (ref "S2") (pin "4") (pinfunction "COMM_2_4") (pintype "bidirectional"))
    )
    (net (code "106") (name "unconnected-(S2-NC_1-Pad1)") (class "Default")
      (node (ref "S2") (pin "1") (pinfunction "NC_1_1") (pintype "bidirectional"))
    )
    (net (code "107") (name "unconnected-(S2-NC_2-Pad6)") (class "Default")
      (node (ref "S2") (pin "6") (pinfunction "NC_2_6") (pintype "bidirectional"))
    )
    (net (code "108") (name "unconnected-(S2-NO_2-Pad5)") (class "Default")
      (node (ref "S2") (pin "5") (pinfunction "NO_2_5") (pintype "bidirectional"))
    )
    (net (code "109") (name "unconnected-(U$100-NC-Pad3)") (class "Default")
      (node (ref "U$100") (pin "3") (pinfunction "NC_3") (pintype "bidirectional"))
    )
    (net (code "110") (name "unconnected-(U$100-NC-Pad18)") (class "Default")
      (node (ref "U$100") (pin "18") (pinfunction "NC_18") (pintype "bidirectional"))
    )
    (net (code "111") (name "unconnected-(U$100-SENSE_A-Pad2)") (class "Default")
      (node (ref "U$100") (pin "2") (pinfunction "SENSE_A_2") (pintype "bidirectional"))
    )
    (net (code "112") (name "unconnected-(U$100-SENSE_B-Pad19)") (class "Default")
      (node (ref "U$100") (pin "19") (pinfunction "SENSE_B_19") (pintype "bidirectional"))
    )
    (net (code "113") (name "unconnected-(U$101-NC-Pad3)") (class "Default")
      (node (ref "U$101") (pin "3") (pinfunction "NC_3") (pintype "bidirectional"))
    )
    (net (code "114") (name "unconnected-(U$101-NC-Pad18)") (class "Default")
      (node (ref "U$101") (pin "18") (pinfunction "NC_18") (pintype "bidirectional"))
    )
    (net (code "115") (name "unconnected-(U$101-SENSE_A-Pad2)") (class "Default")
      (node (ref "U$101") (pin "2") (pinfunction "SENSE_A_2") (pintype "bidirectional"))
    )
    (net (code "116") (name "unconnected-(U$101-SENSE_B-Pad19)") (class "Default")
      (node (ref "U$101") (pin "19") (pinfunction "SENSE_B_19") (pintype "bidirectional"))
    )
  )
)
